# 2.net
KiCad netlist of a schematic drawn in EasyEDA Pro
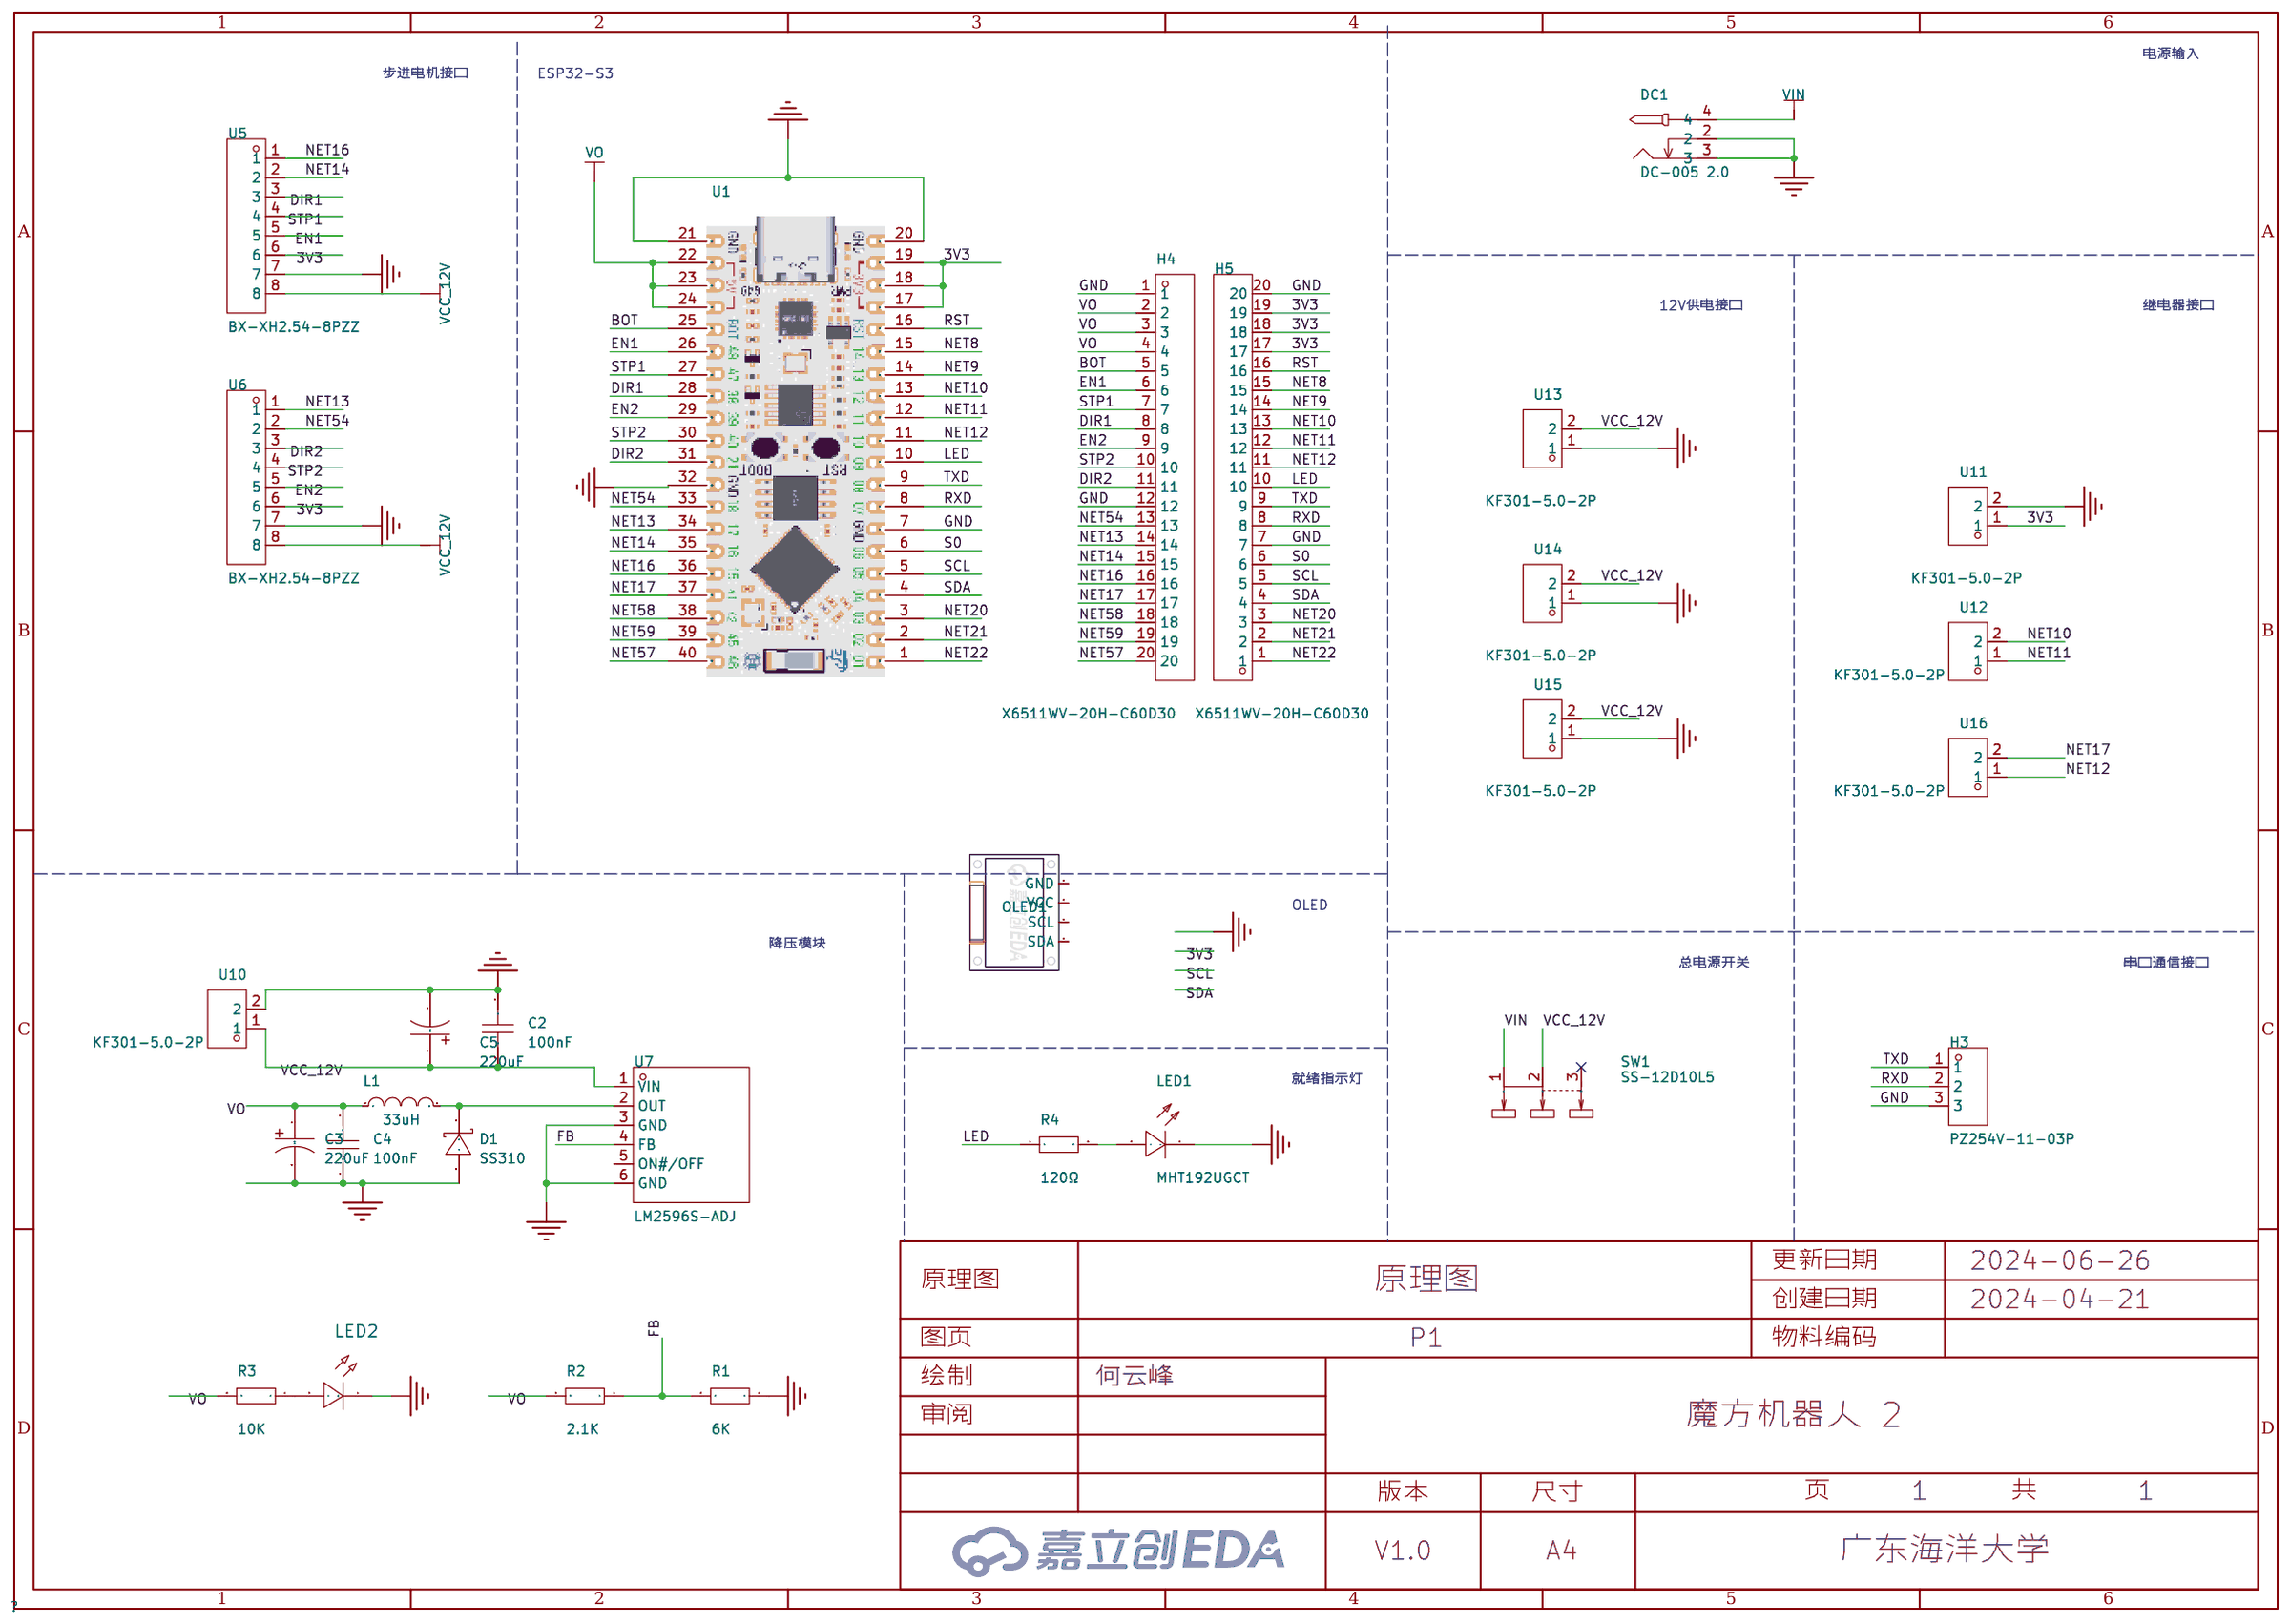
[diagram p0: schematic sheet]

(export (version "E")
  (design (tool "Eeschema 10.0.6"))
  (components
    (comp (ref "C2")
      (value "100nF")
      (footprint "easyedapro:C0805")
      (libsource (lib "easyedapro") (part "CapAcitance"))
    )
    (comp (ref "C3")
      (value "220uF")
      (footprint "easyedapro:CAP-SMD_BD8.0-L8.3-W8.3-FD")
      (fields (field (name "Manufacturer Part") "EEEFP1V221AP") (field (name "Manufacturer") "PANASONIC(松下)"))
      (libsource (lib "easyedapro") (part "EEEFP1V221AP"))
    )
    (comp (ref "C4")
      (value "100nF")
      (footprint "easyedapro:C0805")
      (libsource (lib "easyedapro") (part "CapAcitance"))
    )
    (comp (ref "C5")
      (value "220uF")
      (footprint "easyedapro:CAP-SMD_BD8.0-L8.3-W8.3-FD")
      (fields (field (name "Manufacturer Part") "EEEFP1V221AP") (field (name "Manufacturer") "PANASONIC(松下)"))
      (libsource (lib "easyedapro") (part "EEEFP1V221AP"))
    )
    (comp (ref "D1")
      (value "SS310")
      (footprint "easyedapro:SMA_L4.3-W2.6-LS5.2-RD")
      (description "直流反向耐压(Vr):100V;平均整流电流(Io):3A;正向压降(Vf):850mV@3A;")
      (fields (field (name "Manufacturer") "MDD"))
      (libsource (lib "easyedapro") (part "SS310"))
    )
    (comp (ref "DC1")
      (value "DC-005 2.0")
      (footprint "easyedapro:DC-IN-TH_DC-5520-1")
      (description "连接器类型:DC电源插座;安装方式:弯插;触点内径:2mm;触点外径:6.4mm;额定电流:-;额定电压:-;工作温度范围:-;")
      (fields (field (name "Manufacturer") "BOOMELE(博穆精密)"))
      (libsource (lib "easyedapro") (part "DC-005 5.5-2.0MM"))
    )
    (comp (ref "H3")
      (value "PZ254V-11-03P")
      (footprint "easyedapro:HDR-TH_3P-P2.54-V-M")
      (fields (field (name "Manufacturer") "XFCN(兴飞)"))
      (libsource (lib "easyedapro") (part "PZ254V-11-03P_C2937625"))
    )
    (comp (ref "H4")
      (value "X6511WV-20H-C60D30")
      (footprint "easyedapro:HDR-TH_20P-P2.54-V-M")
      (fields (field (name "Manufacturer") "XKB Connection(中国星坤)"))
      (libsource (lib "easyedapro") (part "X6511WV-20H-C30D60"))
    )
    (comp (ref "H5")
      (value "X6511WV-20H-C60D30")
      (footprint "easyedapro:HDR-TH_20P-P2.54-V-M")
      (fields (field (name "Manufacturer") "XKB Connection(中国星坤)"))
      (libsource (lib "easyedapro") (part "X6511WV-20H-C30D60"))
    )
    (comp (ref "L1")
      (value "33uH")
      (footprint "easyedapro:IND-SMD_L7.0-W6.6_FXL0630")
      (description "电感值:33uH;精度:±20%;额定电流:2A;饱和电流(Isat):2.5A;类型:一体成型电感;")
      (fields (field (name "Manufacturer Part") "FXL0630-330-M") (field (name "Manufacturer") "cjiang(长江微电)"))
      (libsource (lib "easyedapro") (part "FXL0630-330-M"))
    )
    (comp (ref "LED1")
      (value "MHT192UGCT")
      (footprint "easyedapro:LED0603-RD_GREEN")
      (fields (field (name "Manufacturer") "MEIHUA(美华)"))
      (libsource (lib "easyedapro") (part "MHT192UGCT"))
    )
    (comp (ref "LED2")
      (value "~")
      (footprint "easyedapro:LED_0805")
      (libsource (lib "easyedapro") (part "LED_R"))
    )
    (comp (ref "OLED1")
      (value "~")
      (footprint "easyedapro:0.96OLED_4P")
      (libsource (lib "easyedapro") (part "0.96OLED模块_4P"))
    )
    (comp (ref "R1") (value "6K") (footprint "easyedapro:R0805") (libsource (lib "easyedapro") (part "电阻")))
    (comp (ref "R2") (value "2.1K") (footprint "easyedapro:R0805") (libsource (lib "easyedapro") (part "电阻")))
    (comp (ref "R3") (value "10K") (footprint "easyedapro:R0805") (libsource (lib "easyedapro") (part "电阻")))
    (comp (ref "R4")
      (value "120Ω")
      (footprint "easyedapro:R0603")
      (description "电阻类型:厚膜电阻;阻值:120Ω;精度:±1%;功率:100mW;最大工作电压:75V;温度系数:±100ppm/°C;")
      (fields
        (field (name "Manufacturer Part") "0603WAF1200T5E")
        (field (name "Manufacturer") "UNI-ROYAL(厚声)")
      )
      (libsource (lib "easyedapro") (part "0603WAF1200T5E"))
    )
    (comp (ref "SW1")
      (value "SS-12D10L5")
      (footprint "easyedapro:SW-TH_SS-12D10L5")
      (description "电路结构:单刀双掷;安装方式:直插;开关颜色:黑色;额定电流(DC):3A;额定电压(DC):125V;额定电流(AC):3A;额定电压(AC):125V;机械寿命:1万次;")
      (fields (field (name "Manufacturer") "XKB Connectivity(中国星坤)"))
      (libsource (lib "easyedapro") (part "SS-12D10L5"))
    )
    (comp (ref "U1")
      (value "~")
      (footprint "easyedapro:DIP-40_L20.32-W51.66-P2.54-LS15.24_OLD")
      (description "立创·ESP32S3开发板正面芯片面")
      (libsource (lib "easyedapro") (part "立创·ESP32S3开发板"))
    )
    (comp (ref "U5")
      (value "BX-XH2.54-8PZZ")
      (footprint "easyedapro:CONN-TH_8P-P2.50_BX-XH2.54-8PZZ")
      (fields (field (name "Manufacturer") "Bossie(博锡)"))
      (libsource (lib "easyedapro") (part "BX-XH2.54-8PZZ"))
    )
    (comp (ref "U6")
      (value "BX-XH2.54-8PZZ")
      (footprint "easyedapro:CONN-TH_8P-P2.50_BX-XH2.54-8PZZ")
      (fields (field (name "Manufacturer") "Bossie(博锡)"))
      (libsource (lib "easyedapro") (part "BX-XH2.54-8PZZ"))
    )
    (comp (ref "U7")
      (value "LM2596S-ADJ")
      (footprint "easyedapro:TO-263-5_L10.2-W8.6-P1.70-LS14.4-BR")
      (fields (field (name "Manufacturer") "TWGMC(台湾迪嘉)"))
      (libsource (lib "easyedapro") (part "LM2596S-ADJ_C5276751"))
    )
    (comp (ref "U10")
      (value "KF301-5.0-2P")
      (footprint "easyedapro:CONN-TH_P5.00_KF301-5.0-2P")
      (fields (field (name "Manufacturer") "KEFA(科发)"))
      (libsource (lib "easyedapro") (part "KF301-5.0-2P"))
    )
    (comp (ref "U11")
      (value "KF301-5.0-2P")
      (footprint "easyedapro:CONN-TH_P5.00_KF301-5.0-2P")
      (fields (field (name "Manufacturer") "KEFA(科发)"))
      (libsource (lib "easyedapro") (part "KF301-5.0-2P"))
    )
    (comp (ref "U12")
      (value "KF301-5.0-2P")
      (footprint "easyedapro:CONN-TH_P5.00_KF301-5.0-2P")
      (fields (field (name "Manufacturer") "KEFA(科发)"))
      (libsource (lib "easyedapro") (part "KF301-5.0-2P"))
    )
    (comp (ref "U13")
      (value "KF301-5.0-2P")
      (footprint "easyedapro:CONN-TH_P5.00_KF301-5.0-2P")
      (fields (field (name "Manufacturer") "KEFA(科发)"))
      (libsource (lib "easyedapro") (part "KF301-5.0-2P"))
    )
    (comp (ref "U14")
      (value "KF301-5.0-2P")
      (footprint "easyedapro:CONN-TH_P5.00_KF301-5.0-2P")
      (fields (field (name "Manufacturer") "KEFA(科发)"))
      (libsource (lib "easyedapro") (part "KF301-5.0-2P"))
    )
    (comp (ref "U15")
      (value "KF301-5.0-2P")
      (footprint "easyedapro:CONN-TH_P5.00_KF301-5.0-2P")
      (fields (field (name "Manufacturer") "KEFA(科发)"))
      (libsource (lib "easyedapro") (part "KF301-5.0-2P"))
    )
    (comp (ref "U16")
      (value "KF301-5.0-2P")
      (footprint "easyedapro:CONN-TH_P5.00_KF301-5.0-2P")
      (fields (field (name "Manufacturer") "KEFA(科发)"))
      (libsource (lib "easyedapro") (part "KF301-5.0-2P"))
    )
  )
  (nets
    (net (code "1") (name "/3V3") (class "Default")
      (node (ref "H5") (pin "17") (pinfunction "17_17") (pintype "unspecified"))
      (node (ref "H5") (pin "18") (pinfunction "18_18") (pintype "unspecified"))
      (node (ref "H5") (pin "19") (pinfunction "19_19") (pintype "unspecified"))
      (node (ref "U1") (pin "17") (pinfunction "3V3_17") (pintype "input"))
      (node (ref "U1") (pin "18") (pinfunction "3V3_18") (pintype "input"))
      (node (ref "U1") (pin "19") (pinfunction "3V3_19") (pintype "input"))
      (node (ref "U11") (pin "1") (pinfunction "1_1") (pintype "unspecified"))
      (node (ref "U5") (pin "6") (pinfunction "6_6") (pintype "unspecified"))
      (node (ref "U6") (pin "6") (pinfunction "6_6") (pintype "unspecified"))
    )
    (net (code "2") (name "/BOT") (class "Default")
      (node (ref "H4") (pin "5") (pinfunction "5_5") (pintype "unspecified"))
      (node (ref "U1") (pin "25") (pinfunction "RST_25") (pintype "input"))
    )
    (net (code "3") (name "/DIR1") (class "Default")
      (node (ref "H4") (pin "8") (pinfunction "8_8") (pintype "unspecified"))
      (node (ref "U1") (pin "28") (pinfunction "G12_28") (pintype "input"))
      (node (ref "U5") (pin "3") (pinfunction "3_3") (pintype "unspecified"))
    )
    (net (code "4") (name "/DIR2") (class "Default")
      (node (ref "H4") (pin "11") (pinfunction "11_11") (pintype "unspecified"))
      (node (ref "U1") (pin "31") (pinfunction "G09_31") (pintype "input"))
      (node (ref "U6") (pin "3") (pinfunction "3_3") (pintype "unspecified"))
    )
    (net (code "5") (name "/EN1") (class "Default")
      (node (ref "H4") (pin "6") (pinfunction "6_6") (pintype "unspecified"))
      (node (ref "U1") (pin "26") (pinfunction "G14_26") (pintype "input"))
      (node (ref "U5") (pin "5") (pinfunction "5_5") (pintype "unspecified"))
    )
    (net (code "6") (name "/EN2") (class "Default")
      (node (ref "H4") (pin "9") (pinfunction "9_9") (pintype "unspecified"))
      (node (ref "U1") (pin "29") (pinfunction "G11_29") (pintype "input"))
      (node (ref "U6") (pin "5") (pinfunction "5_5") (pintype "unspecified"))
    )
    (net (code "7") (name "/FB") (class "Default")
      (node (ref "R1") (pin "2") (pinfunction "2_2") (pintype "input"))
      (node (ref "R2") (pin "1") (pinfunction "1_1") (pintype "input"))
      (node (ref "U7") (pin "4") (pinfunction "FB_4") (pintype "input"))
    )
    (net (code "8") (name "/LED") (class "Default")
      (node (ref "H5") (pin "10") (pinfunction "10_10") (pintype "unspecified"))
      (node (ref "R4") (pin "1") (pinfunction "1_1") (pintype "input"))
      (node (ref "U1") (pin "10") (pinfunction "G09_10") (pintype "input"))
    )
    (net (code "9") (name "/NET8") (class "Default")
      (node (ref "H5") (pin "15") (pinfunction "15_15") (pintype "unspecified"))
      (node (ref "U1") (pin "15") (pinfunction "G14_15") (pintype "input"))
    )
    (net (code "10") (name "/NET9") (class "Default")
      (node (ref "H5") (pin "14") (pinfunction "14_14") (pintype "unspecified"))
      (node (ref "U1") (pin "14") (pinfunction "G13_14") (pintype "input"))
    )
    (net (code "11") (name "/NET10") (class "Default")
      (node (ref "H5") (pin "13") (pinfunction "13_13") (pintype "unspecified"))
      (node (ref "U1") (pin "13") (pinfunction "G12_13") (pintype "input"))
      (node (ref "U12") (pin "2") (pinfunction "2_2") (pintype "unspecified"))
    )
    (net (code "12") (name "/NET11") (class "Default")
      (node (ref "H5") (pin "12") (pinfunction "12_12") (pintype "unspecified"))
      (node (ref "U1") (pin "12") (pinfunction "G11_12") (pintype "input"))
      (node (ref "U12") (pin "1") (pinfunction "1_1") (pintype "unspecified"))
    )
    (net (code "13") (name "/NET12") (class "Default")
      (node (ref "H5") (pin "11") (pinfunction "11_11") (pintype "unspecified"))
      (node (ref "U1") (pin "11") (pinfunction "G10_11") (pintype "input"))
      (node (ref "U16") (pin "1") (pinfunction "1_1") (pintype "unspecified"))
    )
    (net (code "14") (name "/NET13") (class "Default")
      (node (ref "H4") (pin "14") (pinfunction "14_14") (pintype "unspecified"))
      (node (ref "U1") (pin "34") (pinfunction "GND_34") (pintype "input"))
      (node (ref "U6") (pin "1") (pinfunction "1_1") (pintype "unspecified"))
    )
    (net (code "15") (name "/NET14") (class "Default")
      (node (ref "H4") (pin "15") (pinfunction "15_15") (pintype "unspecified"))
      (node (ref "U1") (pin "35") (pinfunction "G06_35") (pintype "input"))
      (node (ref "U5") (pin "2") (pinfunction "2_2") (pintype "unspecified"))
    )
    (net (code "16") (name "/NET16") (class "Default")
      (node (ref "H4") (pin "16") (pinfunction "16_16") (pintype "unspecified"))
      (node (ref "U1") (pin "36") (pinfunction "G05_36") (pintype "input"))
      (node (ref "U5") (pin "1") (pinfunction "1_1") (pintype "unspecified"))
    )
    (net (code "17") (name "/NET17") (class "Default")
      (node (ref "H4") (pin "17") (pinfunction "17_17") (pintype "unspecified"))
      (node (ref "U1") (pin "37") (pinfunction "G04_37") (pintype "input"))
      (node (ref "U16") (pin "2") (pinfunction "2_2") (pintype "unspecified"))
    )
    (net (code "18") (name "/NET20") (class "Default")
      (node (ref "H5") (pin "3") (pinfunction "3_3") (pintype "unspecified"))
      (node (ref "U1") (pin "3") (pinfunction "G03_3") (pintype "input"))
    )
    (net (code "19") (name "/NET21") (class "Default")
      (node (ref "H5") (pin "2") (pinfunction "2_2") (pintype "unspecified"))
      (node (ref "U1") (pin "2") (pinfunction "G02_2") (pintype "input"))
    )
    (net (code "20") (name "/NET22") (class "Default")
      (node (ref "H5") (pin "1") (pinfunction "1_1") (pintype "unspecified"))
      (node (ref "U1") (pin "1") (pinfunction "G01_1") (pintype "input"))
    )
    (net (code "21") (name "/NET54") (class "Default")
      (node (ref "H4") (pin "13") (pinfunction "13_13") (pintype "unspecified"))
      (node (ref "U1") (pin "33") (pinfunction "G07_33") (pintype "input"))
      (node (ref "U6") (pin "2") (pinfunction "2_2") (pintype "unspecified"))
    )
    (net (code "22") (name "/NET57") (class "Default")
      (node (ref "H4") (pin "20") (pinfunction "20_20") (pintype "unspecified"))
      (node (ref "U1") (pin "40") (pinfunction "G01_40") (pintype "input"))
    )
    (net (code "23") (name "/NET58") (class "Default")
      (node (ref "H4") (pin "18") (pinfunction "18_18") (pintype "unspecified"))
      (node (ref "U1") (pin "38") (pinfunction "G03_38") (pintype "input"))
    )
    (net (code "24") (name "/NET59") (class "Default")
      (node (ref "H4") (pin "19") (pinfunction "19_19") (pintype "unspecified"))
      (node (ref "U1") (pin "39") (pinfunction "G02_39") (pintype "input"))
    )
    (net (code "25") (name "/RST") (class "Default")
      (node (ref "H5") (pin "16") (pinfunction "16_16") (pintype "unspecified"))
      (node (ref "U1") (pin "16") (pinfunction "RST_16") (pintype "input"))
    )
    (net (code "26") (name "/RXD") (class "Default")
      (node (ref "H3") (pin "2") (pinfunction "2_2") (pintype "unspecified"))
      (node (ref "H5") (pin "8") (pinfunction "8_8") (pintype "unspecified"))
      (node (ref "U1") (pin "8") (pinfunction "G07_8") (pintype "input"))
    )
    (net (code "27") (name "/S0") (class "Default")
      (node (ref "H5") (pin "6") (pinfunction "6_6") (pintype "unspecified"))
      (node (ref "U1") (pin "6") (pinfunction "G06_6") (pintype "input"))
    )
    (net (code "28") (name "/SCL") (class "Default")
      (node (ref "H5") (pin "5") (pinfunction "5_5") (pintype "unspecified"))
      (node (ref "U1") (pin "5") (pinfunction "G05_5") (pintype "input"))
    )
    (net (code "29") (name "/SDA") (class "Default")
      (node (ref "H5") (pin "4") (pinfunction "4_4") (pintype "unspecified"))
      (node (ref "U1") (pin "4") (pinfunction "G04_4") (pintype "input"))
    )
    (net (code "30") (name "/STP1") (class "Default")
      (node (ref "H4") (pin "7") (pinfunction "7_7") (pintype "unspecified"))
      (node (ref "U1") (pin "27") (pinfunction "G13_27") (pintype "input"))
      (node (ref "U5") (pin "4") (pinfunction "4_4") (pintype "unspecified"))
    )
    (net (code "31") (name "/STP2") (class "Default")
      (node (ref "H4") (pin "10") (pinfunction "10_10") (pintype "unspecified"))
      (node (ref "U1") (pin "30") (pinfunction "G10_30") (pintype "input"))
      (node (ref "U6") (pin "4") (pinfunction "4_4") (pintype "unspecified"))
    )
    (net (code "32") (name "/TXD") (class "Default")
      (node (ref "H3") (pin "1") (pinfunction "1_1") (pintype "unspecified"))
      (node (ref "H5") (pin "9") (pinfunction "9_9") (pintype "unspecified"))
      (node (ref "U1") (pin "9") (pinfunction "G08_9") (pintype "input"))
    )
    (net (code "33") (name "GND") (class "Default")
      (node (ref "C2") (pin "1") (pinfunction "1_1") (pintype "input"))
      (node (ref "C3") (pin "2") (pinfunction "2_2") (pintype "input"))
      (node (ref "C4") (pin "1") (pinfunction "1_1") (pintype "input"))
      (node (ref "C5") (pin "2") (pinfunction "2_2") (pintype "input"))
      (node (ref "D1") (pin "2") (pinfunction "A_2") (pintype "input"))
      (node (ref "DC1") (pin "2") (pinfunction "2_2") (pintype "unspecified"))
      (node (ref "DC1") (pin "3") (pinfunction "3_3") (pintype "unspecified"))
      (node (ref "H3") (pin "3") (pinfunction "3_3") (pintype "unspecified"))
      (node (ref "H4") (pin "1") (pinfunction "1_1") (pintype "unspecified"))
      (node (ref "H4") (pin "12") (pinfunction "12_12") (pintype "unspecified"))
      (node (ref "H5") (pin "20") (pinfunction "20_20") (pintype "unspecified"))
      (node (ref "H5") (pin "7") (pinfunction "7_7") (pintype "unspecified"))
      (node (ref "LED1") (pin "1") (pinfunction "-_1") (pintype "unspecified"))
      (node (ref "LED2") (pin "1") (pinfunction "C_1") (pintype "input"))
      (node (ref "R1") (pin "1") (pinfunction "1_1") (pintype "input"))
      (node (ref "U1") (pin "20") (pinfunction "GND_20") (pintype "input"))
      (node (ref "U1") (pin "21") (pinfunction "GND_21") (pintype "input"))
      (node (ref "U1") (pin "32") (pinfunction "G08_32") (pintype "input"))
      (node (ref "U1") (pin "7") (pinfunction "GND_7") (pintype "input"))
      (node (ref "U10") (pin "2") (pinfunction "2_2") (pintype "unspecified"))
      (node (ref "U11") (pin "2") (pinfunction "2_2") (pintype "unspecified"))
      (node (ref "U13") (pin "1") (pinfunction "1_1") (pintype "unspecified"))
      (node (ref "U14") (pin "1") (pinfunction "1_1") (pintype "unspecified"))
      (node (ref "U15") (pin "1") (pinfunction "1_1") (pintype "unspecified"))
      (node (ref "U5") (pin "7") (pinfunction "7_7") (pintype "unspecified"))
      (node (ref "U6") (pin "7") (pinfunction "7_7") (pintype "unspecified"))
      (node (ref "U7") (pin "3") (pinfunction "GND_3") (pintype "input"))
      (node (ref "U7") (pin "6") (pinfunction "GND_6") (pintype "input"))
    )
    (net (code "34") (name "Net-(D1-K)") (class "Default")
      (node (ref "D1") (pin "1") (pinfunction "K_1") (pintype "input"))
      (node (ref "L1") (pin "2") (pinfunction "2_2") (pintype "unspecified"))
      (node (ref "U7") (pin "2") (pinfunction "OUT_2") (pintype "input"))
    )
    (net (code "35") (name "Net-(LED1-+)") (class "Default")
      (node (ref "LED1") (pin "2") (pinfunction "+_2") (pintype "unspecified"))
      (node (ref "R4") (pin "2") (pinfunction "2_2") (pintype "input"))
    )
    (net (code "36") (name "Net-(LED2-A)") (class "Default")
      (node (ref "LED2") (pin "2") (pinfunction "A_2") (pintype "input"))
      (node (ref "R3") (pin "1") (pinfunction "1_1") (pintype "input"))
    )
    (net (code "37") (name "VCC_12V") (class "Default")
      (node (ref "C2") (pin "2") (pinfunction "2_2") (pintype "input"))
      (node (ref "C5") (pin "1") (pinfunction "1_1") (pintype "input"))
      (node (ref "SW1") (pin "2") (pinfunction "2_2") (pintype "unspecified"))
      (node (ref "U10") (pin "1") (pinfunction "1_1") (pintype "unspecified"))
      (node (ref "U13") (pin "2") (pinfunction "2_2") (pintype "unspecified"))
      (node (ref "U14") (pin "2") (pinfunction "2_2") (pintype "unspecified"))
      (node (ref "U15") (pin "2") (pinfunction "2_2") (pintype "unspecified"))
      (node (ref "U5") (pin "8") (pinfunction "8_8") (pintype "unspecified"))
      (node (ref "U6") (pin "8") (pinfunction "8_8") (pintype "unspecified"))
      (node (ref "U7") (pin "1") (pinfunction "VIN_1") (pintype "input"))
    )
    (net (code "38") (name "VIN") (class "Default")
      (node (ref "DC1") (pin "4") (pinfunction "4_4") (pintype "unspecified"))
      (node (ref "SW1") (pin "1") (pinfunction "1_1") (pintype "unspecified"))
    )
    (net (code "39") (name "VO") (class "Default")
      (node (ref "C3") (pin "1") (pinfunction "1_1") (pintype "input"))
      (node (ref "C4") (pin "2") (pinfunction "2_2") (pintype "input"))
      (node (ref "H4") (pin "2") (pinfunction "2_2") (pintype "unspecified"))
      (node (ref "H4") (pin "3") (pinfunction "3_3") (pintype "unspecified"))
      (node (ref "H4") (pin "4") (pinfunction "4_4") (pintype "unspecified"))
      (node (ref "L1") (pin "1") (pinfunction "1_1") (pintype "unspecified"))
      (node (ref "R2") (pin "2") (pinfunction "2_2") (pintype "input"))
      (node (ref "R3") (pin "2") (pinfunction "2_2") (pintype "input"))
      (node (ref "U1") (pin "22") (pinfunction "3V3_22") (pintype "input"))
      (node (ref "U1") (pin "23") (pinfunction "3V3_23") (pintype "input"))
      (node (ref "U1") (pin "24") (pinfunction "3V3_24") (pintype "input"))
    )
    (net (code "40") (name "unconnected-(OLED1-GND-Pad1)") (class "Default")
      (node (ref "OLED1") (pin "1") (pinfunction "GND_1") (pintype "input"))
    )
    (net (code "41") (name "unconnected-(OLED1-SCL-Pad3)") (class "Default")
      (node (ref "OLED1") (pin "3") (pinfunction "SCL_3") (pintype "input"))
    )
    (net (code "42") (name "unconnected-(OLED1-SDA-Pad4)") (class "Default")
      (node (ref "OLED1") (pin "4") (pinfunction "SDA_4") (pintype "input"))
    )
    (net (code "43") (name "unconnected-(OLED1-VCC-Pad2)") (class "Default")
      (node (ref "OLED1") (pin "2") (pinfunction "VCC_2") (pintype "input"))
    )
    (net (code "44") (name "unconnected-(SW1-Pad3)") (class "Default")
      (node (ref "SW1") (pin "3") (pinfunction "3_3") (pintype "unspecified+no_connect"))
    )
    (net (code "45") (name "unconnected-(U7-ON#{slash}OFF-Pad5)") (class "Default")
      (node (ref "U7") (pin "5") (pinfunction "ON#/OFF_5") (pintype "input"))
    )
  )
)
